# led_driver_v2.net
KiCad netlist of a schematic drawn in EAGLE
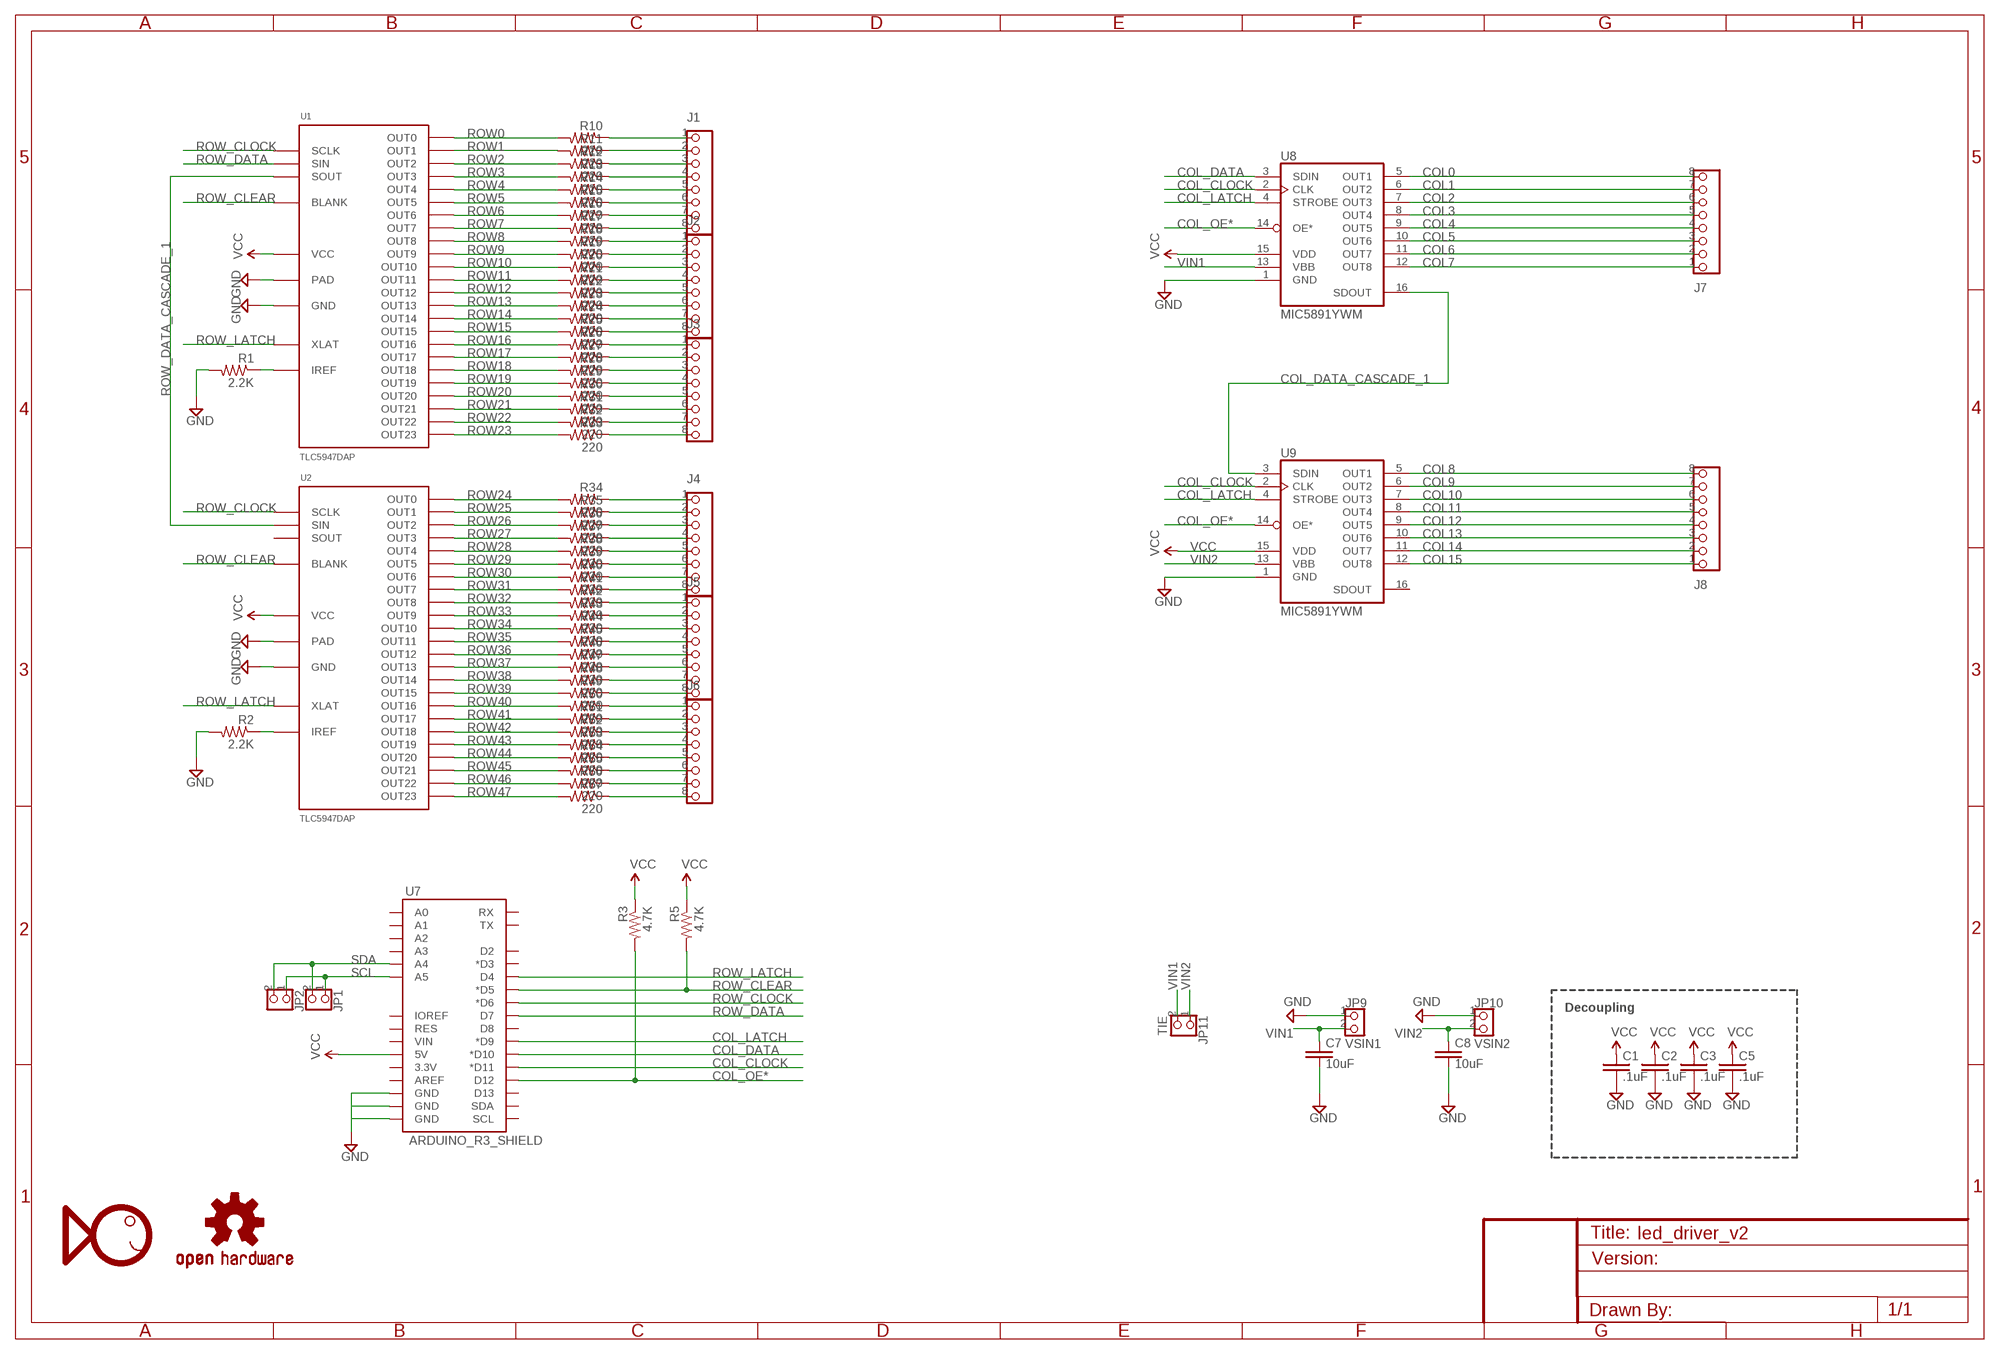
[diagram p0: schematic, sheet 1]

(export (version "E")
  (design (tool "Eeschema 10.0.6"))
  (components
    (comp (ref "C1")
      (value ".1uF")
      (footprint "eagle-import:C0603")
      (libsource (lib "eagle-import") (part "CAPACITORC0603"))
    )
    (comp (ref "C2")
      (value ".1uF")
      (footprint "eagle-import:C0603")
      (libsource (lib "eagle-import") (part "CAPACITORC0603"))
    )
    (comp (ref "C3")
      (value ".1uF")
      (footprint "eagle-import:C0603")
      (libsource (lib "eagle-import") (part "CAPACITORC0603"))
    )
    (comp (ref "C5")
      (value ".1uF")
      (footprint "eagle-import:C0603")
      (libsource (lib "eagle-import") (part "CAPACITORC0603"))
    )
    (comp (ref "C7")
      (value "10uF")
      (footprint "eagle-import:C0603")
      (libsource (lib "eagle-import") (part "CAPACITORC0603"))
    )
    (comp (ref "C8")
      (value "10uF")
      (footprint "eagle-import:C0603")
      (libsource (lib "eagle-import") (part "CAPACITORC0603"))
    )
    (comp (ref "FHI_LOGO")
      (value "FHI_LOGO")
      (footprint "eagle-import:FHI_LOGO")
      (libsource (lib "eagle-import") (part "FHI_LOGO"))
    )
    (comp (ref "J1")
      (value "PINHD-1X8")
      (footprint "eagle-import:1X08")
      (libsource (lib "eagle-import") (part "PINHD-1X8"))
    )
    (comp (ref "J2")
      (value "PINHD-1X8")
      (footprint "eagle-import:1X08")
      (libsource (lib "eagle-import") (part "PINHD-1X8"))
    )
    (comp (ref "J3")
      (value "PINHD-1X8")
      (footprint "eagle-import:1X08")
      (libsource (lib "eagle-import") (part "PINHD-1X8"))
    )
    (comp (ref "J4")
      (value "PINHD-1X8")
      (footprint "eagle-import:1X08")
      (libsource (lib "eagle-import") (part "PINHD-1X8"))
    )
    (comp (ref "J5")
      (value "PINHD-1X8")
      (footprint "eagle-import:1X08")
      (libsource (lib "eagle-import") (part "PINHD-1X8"))
    )
    (comp (ref "J6")
      (value "PINHD-1X8")
      (footprint "eagle-import:1X08")
      (libsource (lib "eagle-import") (part "PINHD-1X8"))
    )
    (comp (ref "J7")
      (value "PINHD-1X8")
      (footprint "eagle-import:1X08")
      (libsource (lib "eagle-import") (part "PINHD-1X8"))
    )
    (comp (ref "J8")
      (value "PINHD-1X8")
      (footprint "eagle-import:1X08")
      (libsource (lib "eagle-import") (part "PINHD-1X8"))
    )
    (comp (ref "JP1")
      (value "PINHD-1X2")
      (footprint "eagle-import:1X02")
      (libsource (lib "eagle-import") (part "PINHD-1X2"))
    )
    (comp (ref "JP2")
      (value "PINHD-1X2")
      (footprint "eagle-import:1X02")
      (libsource (lib "eagle-import") (part "PINHD-1X2"))
    )
    (comp (ref "JP9")
      (value "VSIN1")
      (footprint "eagle-import:1X02")
      (libsource (lib "eagle-import") (part "PINHD-1X2"))
    )
    (comp (ref "JP10")
      (value "VSIN2")
      (footprint "eagle-import:1X02")
      (libsource (lib "eagle-import") (part "PINHD-1X2"))
    )
    (comp (ref "JP11")
      (value "TIE")
      (footprint "eagle-import:1X02")
      (libsource (lib "eagle-import") (part "PINHD-1X2"))
    )
    (comp (ref "OHW_LOGO")
      (value "OSHW-LOGOS")
      (footprint "eagle-import:OSHW-LOGO-S")
      (libsource (lib "eagle-import") (part "OSHW-LOGOS"))
    )
    (comp (ref "R1")
      (value "2.2K")
      (footprint "eagle-import:0603-RES")
      (libsource (lib "eagle-import") (part "RESISTOR_SMD0603-RES"))
    )
    (comp (ref "R2")
      (value "2.2K")
      (footprint "eagle-import:0603-RES")
      (libsource (lib "eagle-import") (part "RESISTOR_SMD0603-RES"))
    )
    (comp (ref "R3")
      (value "4.7K")
      (footprint "eagle-import:0603-RES")
      (libsource (lib "eagle-import") (part "RESISTOR_SMD0603-RES"))
    )
    (comp (ref "R5")
      (value "4.7K")
      (footprint "eagle-import:0603-RES")
      (libsource (lib "eagle-import") (part "RESISTOR_SMD0603-RES"))
    )
    (comp (ref "R10")
      (value "220")
      (footprint "eagle-import:0603-RES")
      (libsource (lib "eagle-import") (part "RESISTOR_SMD0603-RES"))
    )
    (comp (ref "R11")
      (value "220")
      (footprint "eagle-import:0603-RES")
      (libsource (lib "eagle-import") (part "RESISTOR_SMD0603-RES"))
    )
    (comp (ref "R12")
      (value "220")
      (footprint "eagle-import:0603-RES")
      (libsource (lib "eagle-import") (part "RESISTOR_SMD0603-RES"))
    )
    (comp (ref "R13")
      (value "220")
      (footprint "eagle-import:0603-RES")
      (libsource (lib "eagle-import") (part "RESISTOR_SMD0603-RES"))
    )
    (comp (ref "R14")
      (value "220")
      (footprint "eagle-import:0603-RES")
      (libsource (lib "eagle-import") (part "RESISTOR_SMD0603-RES"))
    )
    (comp (ref "R15")
      (value "220")
      (footprint "eagle-import:0603-RES")
      (libsource (lib "eagle-import") (part "RESISTOR_SMD0603-RES"))
    )
    (comp (ref "R16")
      (value "220")
      (footprint "eagle-import:0603-RES")
      (libsource (lib "eagle-import") (part "RESISTOR_SMD0603-RES"))
    )
    (comp (ref "R17")
      (value "220")
      (footprint "eagle-import:0603-RES")
      (libsource (lib "eagle-import") (part "RESISTOR_SMD0603-RES"))
    )
    (comp (ref "R18")
      (value "220")
      (footprint "eagle-import:0603-RES")
      (libsource (lib "eagle-import") (part "RESISTOR_SMD0603-RES"))
    )
    (comp (ref "R19")
      (value "220")
      (footprint "eagle-import:0603-RES")
      (libsource (lib "eagle-import") (part "RESISTOR_SMD0603-RES"))
    )
    (comp (ref "R20")
      (value "220")
      (footprint "eagle-import:0603-RES")
      (libsource (lib "eagle-import") (part "RESISTOR_SMD0603-RES"))
    )
    (comp (ref "R21")
      (value "220")
      (footprint "eagle-import:0603-RES")
      (libsource (lib "eagle-import") (part "RESISTOR_SMD0603-RES"))
    )
    (comp (ref "R22")
      (value "220")
      (footprint "eagle-import:0603-RES")
      (libsource (lib "eagle-import") (part "RESISTOR_SMD0603-RES"))
    )
    (comp (ref "R23")
      (value "220")
      (footprint "eagle-import:0603-RES")
      (libsource (lib "eagle-import") (part "RESISTOR_SMD0603-RES"))
    )
    (comp (ref "R24")
      (value "220")
      (footprint "eagle-import:0603-RES")
      (libsource (lib "eagle-import") (part "RESISTOR_SMD0603-RES"))
    )
    (comp (ref "R25")
      (value "220")
      (footprint "eagle-import:0603-RES")
      (libsource (lib "eagle-import") (part "RESISTOR_SMD0603-RES"))
    )
    (comp (ref "R26")
      (value "220")
      (footprint "eagle-import:0603-RES")
      (libsource (lib "eagle-import") (part "RESISTOR_SMD0603-RES"))
    )
    (comp (ref "R27")
      (value "220")
      (footprint "eagle-import:0603-RES")
      (libsource (lib "eagle-import") (part "RESISTOR_SMD0603-RES"))
    )
    (comp (ref "R28")
      (value "220")
      (footprint "eagle-import:0603-RES")
      (libsource (lib "eagle-import") (part "RESISTOR_SMD0603-RES"))
    )
    (comp (ref "R29")
      (value "220")
      (footprint "eagle-import:0603-RES")
      (libsource (lib "eagle-import") (part "RESISTOR_SMD0603-RES"))
    )
    (comp (ref "R30")
      (value "220")
      (footprint "eagle-import:0603-RES")
      (libsource (lib "eagle-import") (part "RESISTOR_SMD0603-RES"))
    )
    (comp (ref "R31")
      (value "220")
      (footprint "eagle-import:0603-RES")
      (libsource (lib "eagle-import") (part "RESISTOR_SMD0603-RES"))
    )
    (comp (ref "R32")
      (value "220")
      (footprint "eagle-import:0603-RES")
      (libsource (lib "eagle-import") (part "RESISTOR_SMD0603-RES"))
    )
    (comp (ref "R33")
      (value "220")
      (footprint "eagle-import:0603-RES")
      (libsource (lib "eagle-import") (part "RESISTOR_SMD0603-RES"))
    )
    (comp (ref "R34")
      (value "220")
      (footprint "eagle-import:0603-RES")
      (libsource (lib "eagle-import") (part "RESISTOR_SMD0603-RES"))
    )
    (comp (ref "R35")
      (value "220")
      (footprint "eagle-import:0603-RES")
      (libsource (lib "eagle-import") (part "RESISTOR_SMD0603-RES"))
    )
    (comp (ref "R36")
      (value "220")
      (footprint "eagle-import:0603-RES")
      (libsource (lib "eagle-import") (part "RESISTOR_SMD0603-RES"))
    )
    (comp (ref "R37")
      (value "220")
      (footprint "eagle-import:0603-RES")
      (libsource (lib "eagle-import") (part "RESISTOR_SMD0603-RES"))
    )
    (comp (ref "R38")
      (value "220")
      (footprint "eagle-import:0603-RES")
      (libsource (lib "eagle-import") (part "RESISTOR_SMD0603-RES"))
    )
    (comp (ref "R39")
      (value "220")
      (footprint "eagle-import:0603-RES")
      (libsource (lib "eagle-import") (part "RESISTOR_SMD0603-RES"))
    )
    (comp (ref "R40")
      (value "220")
      (footprint "eagle-import:0603-RES")
      (libsource (lib "eagle-import") (part "RESISTOR_SMD0603-RES"))
    )
    (comp (ref "R41")
      (value "220")
      (footprint "eagle-import:0603-RES")
      (libsource (lib "eagle-import") (part "RESISTOR_SMD0603-RES"))
    )
    (comp (ref "R42")
      (value "220")
      (footprint "eagle-import:0603-RES")
      (libsource (lib "eagle-import") (part "RESISTOR_SMD0603-RES"))
    )
    (comp (ref "R43")
      (value "220")
      (footprint "eagle-import:0603-RES")
      (libsource (lib "eagle-import") (part "RESISTOR_SMD0603-RES"))
    )
    (comp (ref "R44")
      (value "220")
      (footprint "eagle-import:0603-RES")
      (libsource (lib "eagle-import") (part "RESISTOR_SMD0603-RES"))
    )
    (comp (ref "R45")
      (value "220")
      (footprint "eagle-import:0603-RES")
      (libsource (lib "eagle-import") (part "RESISTOR_SMD0603-RES"))
    )
    (comp (ref "R46")
      (value "220")
      (footprint "eagle-import:0603-RES")
      (libsource (lib "eagle-import") (part "RESISTOR_SMD0603-RES"))
    )
    (comp (ref "R47")
      (value "220")
      (footprint "eagle-import:0603-RES")
      (libsource (lib "eagle-import") (part "RESISTOR_SMD0603-RES"))
    )
    (comp (ref "R48")
      (value "220")
      (footprint "eagle-import:0603-RES")
      (libsource (lib "eagle-import") (part "RESISTOR_SMD0603-RES"))
    )
    (comp (ref "R49")
      (value "220")
      (footprint "eagle-import:0603-RES")
      (libsource (lib "eagle-import") (part "RESISTOR_SMD0603-RES"))
    )
    (comp (ref "R50")
      (value "220")
      (footprint "eagle-import:0603-RES")
      (libsource (lib "eagle-import") (part "RESISTOR_SMD0603-RES"))
    )
    (comp (ref "R51")
      (value "220")
      (footprint "eagle-import:0603-RES")
      (libsource (lib "eagle-import") (part "RESISTOR_SMD0603-RES"))
    )
    (comp (ref "R52")
      (value "220")
      (footprint "eagle-import:0603-RES")
      (libsource (lib "eagle-import") (part "RESISTOR_SMD0603-RES"))
    )
    (comp (ref "R53")
      (value "220")
      (footprint "eagle-import:0603-RES")
      (libsource (lib "eagle-import") (part "RESISTOR_SMD0603-RES"))
    )
    (comp (ref "R54")
      (value "220")
      (footprint "eagle-import:0603-RES")
      (libsource (lib "eagle-import") (part "RESISTOR_SMD0603-RES"))
    )
    (comp (ref "R55")
      (value "220")
      (footprint "eagle-import:0603-RES")
      (libsource (lib "eagle-import") (part "RESISTOR_SMD0603-RES"))
    )
    (comp (ref "R56")
      (value "220")
      (footprint "eagle-import:0603-RES")
      (libsource (lib "eagle-import") (part "RESISTOR_SMD0603-RES"))
    )
    (comp (ref "R57")
      (value "220")
      (footprint "eagle-import:0603-RES")
      (libsource (lib "eagle-import") (part "RESISTOR_SMD0603-RES"))
    )
    (comp (ref "U1")
      (value "TLC5947DAP")
      (footprint "eagle-import:HTSSOP32DAP")
      (libsource (lib "eagle-import") (part "TLC5947DAP"))
    )
    (comp (ref "U2")
      (value "TLC5947DAP")
      (footprint "eagle-import:HTSSOP32DAP")
      (libsource (lib "eagle-import") (part "TLC5947DAP"))
    )
    (comp (ref "U7")
      (value "ARDUINO_R3_SHIELD")
      (footprint "eagle-import:UNO_R3_SHIELD")
      (libsource (lib "eagle-import") (part "ARDUINO_R3_SHIELD"))
    )
    (comp (ref "U8")
      (value "MIC5891YWM")
      (footprint "eagle-import:SO16")
      (libsource (lib "eagle-import") (part "MIC5891YWM"))
    )
    (comp (ref "U9")
      (value "MIC5891YWM")
      (footprint "eagle-import:SO16")
      (libsource (lib "eagle-import") (part "MIC5891YWM"))
    )
  )
  (nets
    (net (code "1") (name "/COL0") (class "Default")
      (node (ref "J7") (pin "8") (pinfunction "8_8") (pintype "passive"))
      (node (ref "U8") (pin "5") (pinfunction "OUT1_5") (pintype "tri_state"))
    )
    (net (code "2") (name "/COL1") (class "Default")
      (node (ref "J7") (pin "7") (pinfunction "7_7") (pintype "passive"))
      (node (ref "U8") (pin "6") (pinfunction "OUT2_6") (pintype "tri_state"))
    )
    (net (code "3") (name "/COL2") (class "Default")
      (node (ref "J7") (pin "6") (pinfunction "6_6") (pintype "passive"))
      (node (ref "U8") (pin "7") (pinfunction "OUT3_7") (pintype "tri_state"))
    )
    (net (code "4") (name "/COL3") (class "Default")
      (node (ref "J7") (pin "5") (pinfunction "5_5") (pintype "passive"))
      (node (ref "U8") (pin "8") (pinfunction "OUT4_8") (pintype "tri_state"))
    )
    (net (code "5") (name "/COL4") (class "Default")
      (node (ref "J7") (pin "4") (pinfunction "4_4") (pintype "passive"))
      (node (ref "U8") (pin "9") (pinfunction "OUT5_9") (pintype "tri_state"))
    )
    (net (code "6") (name "/COL5") (class "Default")
      (node (ref "J7") (pin "3") (pinfunction "3_3") (pintype "passive"))
      (node (ref "U8") (pin "10") (pinfunction "OUT6_10") (pintype "tri_state"))
    )
    (net (code "7") (name "/COL6") (class "Default")
      (node (ref "J7") (pin "2") (pinfunction "2_2") (pintype "passive"))
      (node (ref "U8") (pin "11") (pinfunction "OUT7_11") (pintype "tri_state"))
    )
    (net (code "8") (name "/COL7") (class "Default")
      (node (ref "J7") (pin "1") (pinfunction "1_1") (pintype "passive"))
      (node (ref "U8") (pin "12") (pinfunction "OUT8_12") (pintype "tri_state"))
    )
    (net (code "9") (name "/COL8") (class "Default")
      (node (ref "J8") (pin "8") (pinfunction "8_8") (pintype "passive"))
      (node (ref "U9") (pin "5") (pinfunction "OUT1_5") (pintype "tri_state"))
    )
    (net (code "10") (name "/COL9") (class "Default")
      (node (ref "J8") (pin "7") (pinfunction "7_7") (pintype "passive"))
      (node (ref "U9") (pin "6") (pinfunction "OUT2_6") (pintype "tri_state"))
    )
    (net (code "11") (name "/COL10") (class "Default")
      (node (ref "J8") (pin "6") (pinfunction "6_6") (pintype "passive"))
      (node (ref "U9") (pin "7") (pinfunction "OUT3_7") (pintype "tri_state"))
    )
    (net (code "12") (name "/COL11") (class "Default")
      (node (ref "J8") (pin "5") (pinfunction "5_5") (pintype "passive"))
      (node (ref "U9") (pin "8") (pinfunction "OUT4_8") (pintype "tri_state"))
    )
    (net (code "13") (name "/COL12") (class "Default")
      (node (ref "J8") (pin "4") (pinfunction "4_4") (pintype "passive"))
      (node (ref "U9") (pin "9") (pinfunction "OUT5_9") (pintype "tri_state"))
    )
    (net (code "14") (name "/COL13") (class "Default")
      (node (ref "J8") (pin "3") (pinfunction "3_3") (pintype "passive"))
      (node (ref "U9") (pin "10") (pinfunction "OUT6_10") (pintype "tri_state"))
    )
    (net (code "15") (name "/COL14") (class "Default")
      (node (ref "J8") (pin "2") (pinfunction "2_2") (pintype "passive"))
      (node (ref "U9") (pin "11") (pinfunction "OUT7_11") (pintype "tri_state"))
    )
    (net (code "16") (name "/COL15") (class "Default")
      (node (ref "J8") (pin "1") (pinfunction "1_1") (pintype "passive"))
      (node (ref "U9") (pin "12") (pinfunction "OUT8_12") (pintype "tri_state"))
    )
    (net (code "17") (name "/COL_CLOCK") (class "Default")
      (node (ref "U7") (pin "D11") (pinfunction "*D11_D11") (pintype "bidirectional"))
      (node (ref "U8") (pin "2") (pinfunction "CLK_2") (pintype "input"))
      (node (ref "U9") (pin "2") (pinfunction "CLK_2") (pintype "input"))
    )
    (net (code "18") (name "/COL_DATA") (class "Default")
      (node (ref "U7") (pin "D10") (pinfunction "*D10_D10") (pintype "bidirectional"))
      (node (ref "U8") (pin "3") (pinfunction "SDIN_3") (pintype "input"))
    )
    (net (code "19") (name "/COL_DATA_CASCADE_1") (class "Default")
      (node (ref "U8") (pin "16") (pinfunction "SDOUT_16") (pintype "output"))
      (node (ref "U9") (pin "3") (pinfunction "SDIN_3") (pintype "input"))
    )
    (net (code "20") (name "/COL_LATCH") (class "Default")
      (node (ref "U7") (pin "D9") (pinfunction "*D9_D9") (pintype "bidirectional"))
      (node (ref "U8") (pin "4") (pinfunction "STROBE_4") (pintype "input"))
      (node (ref "U9") (pin "4") (pinfunction "STROBE_4") (pintype "input"))
    )
    (net (code "21") (name "/COL_OE*") (class "Default")
      (node (ref "R3") (pin "2") (pinfunction "2_2") (pintype "passive"))
      (node (ref "U7") (pin "D12") (pinfunction "D12_D12") (pintype "bidirectional"))
      (node (ref "U8") (pin "14") (pinfunction "OE*_14") (pintype "input"))
      (node (ref "U9") (pin "14") (pinfunction "OE*_14") (pintype "input"))
    )
    (net (code "22") (name "/ROW0") (class "Default")
      (node (ref "R10") (pin "2") (pinfunction "2_2") (pintype "passive"))
      (node (ref "U1") (pin "5") (pinfunction "OUT0_5") (pintype "bidirectional"))
    )
    (net (code "23") (name "/ROW1") (class "Default")
      (node (ref "R11") (pin "2") (pinfunction "2_2") (pintype "passive"))
      (node (ref "U1") (pin "6") (pinfunction "OUT1_6") (pintype "bidirectional"))
    )
    (net (code "24") (name "/ROW2") (class "Default")
      (node (ref "R12") (pin "2") (pinfunction "2_2") (pintype "passive"))
      (node (ref "U1") (pin "7") (pinfunction "OUT2_7") (pintype "bidirectional"))
    )
    (net (code "25") (name "/ROW3") (class "Default")
      (node (ref "R13") (pin "2") (pinfunction "2_2") (pintype "passive"))
      (node (ref "U1") (pin "8") (pinfunction "OUT3_8") (pintype "bidirectional"))
    )
    (net (code "26") (name "/ROW4") (class "Default")
      (node (ref "R14") (pin "2") (pinfunction "2_2") (pintype "passive"))
      (node (ref "U1") (pin "9") (pinfunction "OUT4_9") (pintype "bidirectional"))
    )
    (net (code "27") (name "/ROW5") (class "Default")
      (node (ref "R15") (pin "2") (pinfunction "2_2") (pintype "passive"))
      (node (ref "U1") (pin "10") (pinfunction "OUT5_10") (pintype "bidirectional"))
    )
    (net (code "28") (name "/ROW6") (class "Default")
      (node (ref "R16") (pin "2") (pinfunction "2_2") (pintype "passive"))
      (node (ref "U1") (pin "11") (pinfunction "OUT6_11") (pintype "bidirectional"))
    )
    (net (code "29") (name "/ROW7") (class "Default")
      (node (ref "R17") (pin "2") (pinfunction "2_2") (pintype "passive"))
      (node (ref "U1") (pin "12") (pinfunction "OUT7_12") (pintype "bidirectional"))
    )
    (net (code "30") (name "/ROW8") (class "Default")
      (node (ref "R18") (pin "2") (pinfunction "2_2") (pintype "passive"))
      (node (ref "U1") (pin "13") (pinfunction "OUT8_13") (pintype "bidirectional"))
    )
    (net (code "31") (name "/ROW9") (class "Default")
      (node (ref "R19") (pin "2") (pinfunction "2_2") (pintype "passive"))
      (node (ref "U1") (pin "14") (pinfunction "OUT9_14") (pintype "bidirectional"))
    )
    (net (code "32") (name "/ROW10") (class "Default")
      (node (ref "R20") (pin "2") (pinfunction "2_2") (pintype "passive"))
      (node (ref "U1") (pin "15") (pinfunction "OUT10_15") (pintype "bidirectional"))
    )
    (net (code "33") (name "/ROW11") (class "Default")
      (node (ref "R21") (pin "2") (pinfunction "2_2") (pintype "passive"))
      (node (ref "U1") (pin "16") (pinfunction "OUT11_16") (pintype "bidirectional"))
    )
    (net (code "34") (name "/ROW12") (class "Default")
      (node (ref "R22") (pin "2") (pinfunction "2_2") (pintype "passive"))
      (node (ref "U1") (pin "17") (pinfunction "OUT12_17") (pintype "bidirectional"))
    )
    (net (code "35") (name "/ROW13") (class "Default")
      (node (ref "R23") (pin "2") (pinfunction "2_2") (pintype "passive"))
      (node (ref "U1") (pin "18") (pinfunction "OUT13_18") (pintype "bidirectional"))
    )
    (net (code "36") (name "/ROW14") (class "Default")
      (node (ref "R24") (pin "2") (pinfunction "2_2") (pintype "passive"))
      (node (ref "U1") (pin "19") (pinfunction "OUT14_19") (pintype "bidirectional"))
    )
    (net (code "37") (name "/ROW15") (class "Default")
      (node (ref "R25") (pin "2") (pinfunction "2_2") (pintype "passive"))
      (node (ref "U1") (pin "20") (pinfunction "OUT15_20") (pintype "bidirectional"))
    )
    (net (code "38") (name "/ROW16") (class "Default")
      (node (ref "R26") (pin "2") (pinfunction "2_2") (pintype "passive"))
      (node (ref "U1") (pin "21") (pinfunction "OUT16_21") (pintype "bidirectional"))
    )
    (net (code "39") (name "/ROW17") (class "Default")
      (node (ref "R27") (pin "2") (pinfunction "2_2") (pintype "passive"))
      (node (ref "U1") (pin "22") (pinfunction "OUT17_22") (pintype "bidirectional"))
    )
    (net (code "40") (name "/ROW18") (class "Default")
      (node (ref "R28") (pin "2") (pinfunction "2_2") (pintype "passive"))
      (node (ref "U1") (pin "23") (pinfunction "OUT18_23") (pintype "bidirectional"))
    )
    (net (code "41") (name "/ROW19") (class "Default")
      (node (ref "R29") (pin "2") (pinfunction "2_2") (pintype "passive"))
      (node (ref "U1") (pin "24") (pinfunction "OUT19_24") (pintype "bidirectional"))
    )
    (net (code "42") (name "/ROW20") (class "Default")
      (node (ref "R30") (pin "2") (pinfunction "2_2") (pintype "passive"))
      (node (ref "U1") (pin "25") (pinfunction "OUT20_25") (pintype "bidirectional"))
    )
    (net (code "43") (name "/ROW21") (class "Default")
      (node (ref "R31") (pin "2") (pinfunction "2_2") (pintype "passive"))
      (node (ref "U1") (pin "26") (pinfunction "OUT21_26") (pintype "bidirectional"))
    )
    (net (code "44") (name "/ROW22") (class "Default")
      (node (ref "R32") (pin "2") (pinfunction "2_2") (pintype "passive"))
      (node (ref "U1") (pin "27") (pinfunction "OUT22_27") (pintype "bidirectional"))
    )
    (net (code "45") (name "/ROW23") (class "Default")
      (node (ref "R33") (pin "2") (pinfunction "2_2") (pintype "passive"))
      (node (ref "U1") (pin "28") (pinfunction "OUT23_28") (pintype "bidirectional"))
    )
    (net (code "46") (name "/ROW24") (class "Default")
      (node (ref "R34") (pin "2") (pinfunction "2_2") (pintype "passive"))
      (node (ref "U2") (pin "5") (pinfunction "OUT0_5") (pintype "bidirectional"))
    )
    (net (code "47") (name "/ROW25") (class "Default")
      (node (ref "R35") (pin "2") (pinfunction "2_2") (pintype "passive"))
      (node (ref "U2") (pin "6") (pinfunction "OUT1_6") (pintype "bidirectional"))
    )
    (net (code "48") (name "/ROW26") (class "Default")
      (node (ref "R36") (pin "2") (pinfunction "2_2") (pintype "passive"))
      (node (ref "U2") (pin "7") (pinfunction "OUT2_7") (pintype "bidirectional"))
    )
    (net (code "49") (name "/ROW27") (class "Default")
      (node (ref "R37") (pin "2") (pinfunction "2_2") (pintype "passive"))
      (node (ref "U2") (pin "8") (pinfunction "OUT3_8") (pintype "bidirectional"))
    )
    (net (code "50") (name "/ROW28") (class "Default")
      (node (ref "R38") (pin "2") (pinfunction "2_2") (pintype "passive"))
      (node (ref "U2") (pin "9") (pinfunction "OUT4_9") (pintype "bidirectional"))
    )
    (net (code "51") (name "/ROW29") (class "Default")
      (node (ref "R39") (pin "2") (pinfunction "2_2") (pintype "passive"))
      (node (ref "U2") (pin "10") (pinfunction "OUT5_10") (pintype "bidirectional"))
    )
    (net (code "52") (name "/ROW30") (class "Default")
      (node (ref "R40") (pin "2") (pinfunction "2_2") (pintype "passive"))
      (node (ref "U2") (pin "11") (pinfunction "OUT6_11") (pintype "bidirectional"))
    )
    (net (code "53") (name "/ROW31") (class "Default")
      (node (ref "R41") (pin "2") (pinfunction "2_2") (pintype "passive"))
      (node (ref "U2") (pin "12") (pinfunction "OUT7_12") (pintype "bidirectional"))
    )
    (net (code "54") (name "/ROW32") (class "Default")
      (node (ref "R42") (pin "2") (pinfunction "2_2") (pintype "passive"))
      (node (ref "U2") (pin "13") (pinfunction "OUT8_13") (pintype "bidirectional"))
    )
    (net (code "55") (name "/ROW33") (class "Default")
      (node (ref "R43") (pin "2") (pinfunction "2_2") (pintype "passive"))
      (node (ref "U2") (pin "14") (pinfunction "OUT9_14") (pintype "bidirectional"))
    )
    (net (code "56") (name "/ROW34") (class "Default")
      (node (ref "R44") (pin "2") (pinfunction "2_2") (pintype "passive"))
      (node (ref "U2") (pin "15") (pinfunction "OUT10_15") (pintype "bidirectional"))
    )
    (net (code "57") (name "/ROW35") (class "Default")
      (node (ref "R45") (pin "2") (pinfunction "2_2") (pintype "passive"))
      (node (ref "U2") (pin "16") (pinfunction "OUT11_16") (pintype "bidirectional"))
    )
    (net (code "58") (name "/ROW36") (class "Default")
      (node (ref "R46") (pin "2") (pinfunction "2_2") (pintype "passive"))
      (node (ref "U2") (pin "17") (pinfunction "OUT12_17") (pintype "bidirectional"))
    )
    (net (code "59") (name "/ROW37") (class "Default")
      (node (ref "R47") (pin "2") (pinfunction "2_2") (pintype "passive"))
      (node (ref "U2") (pin "18") (pinfunction "OUT13_18") (pintype "bidirectional"))
    )
    (net (code "60") (name "/ROW38") (class "Default")
      (node (ref "R48") (pin "2") (pinfunction "2_2") (pintype "passive"))
      (node (ref "U2") (pin "19") (pinfunction "OUT14_19") (pintype "bidirectional"))
    )
    (net (code "61") (name "/ROW39") (class "Default")
      (node (ref "R49") (pin "2") (pinfunction "2_2") (pintype "passive"))
      (node (ref "U2") (pin "20") (pinfunction "OUT15_20") (pintype "bidirectional"))
    )
    (net (code "62") (name "/ROW40") (class "Default")
      (node (ref "R50") (pin "2") (pinfunction "2_2") (pintype "passive"))
      (node (ref "U2") (pin "21") (pinfunction "OUT16_21") (pintype "bidirectional"))
    )
    (net (code "63") (name "/ROW41") (class "Default")
      (node (ref "R51") (pin "2") (pinfunction "2_2") (pintype "passive"))
      (node (ref "U2") (pin "22") (pinfunction "OUT17_22") (pintype "bidirectional"))
    )
    (net (code "64") (name "/ROW42") (class "Default")
      (node (ref "R52") (pin "2") (pinfunction "2_2") (pintype "passive"))
      (node (ref "U2") (pin "23") (pinfunction "OUT18_23") (pintype "bidirectional"))
    )
    (net (code "65") (name "/ROW43") (class "Default")
      (node (ref "R53") (pin "2") (pinfunction "2_2") (pintype "passive"))
      (node (ref "U2") (pin "24") (pinfunction "OUT19_24") (pintype "bidirectional"))
    )
    (net (code "66") (name "/ROW44") (class "Default")
      (node (ref "R54") (pin "2") (pinfunction "2_2") (pintype "passive"))
      (node (ref "U2") (pin "25") (pinfunction "OUT20_25") (pintype "bidirectional"))
    )
    (net (code "67") (name "/ROW45") (class "Default")
      (node (ref "R55") (pin "2") (pinfunction "2_2") (pintype "passive"))
      (node (ref "U2") (pin "26") (pinfunction "OUT21_26") (pintype "bidirectional"))
    )
    (net (code "68") (name "/ROW46") (class "Default")
      (node (ref "R56") (pin "2") (pinfunction "2_2") (pintype "passive"))
      (node (ref "U2") (pin "27") (pinfunction "OUT22_27") (pintype "bidirectional"))
    )
    (net (code "69") (name "/ROW47") (class "Default")
      (node (ref "R57") (pin "2") (pinfunction "2_2") (pintype "passive"))
      (node (ref "U2") (pin "28") (pinfunction "OUT23_28") (pintype "bidirectional"))
    )
    (net (code "70") (name "/ROW_CLEAR") (class "Default")
      (node (ref "R5") (pin "2") (pinfunction "2_2") (pintype "passive"))
      (node (ref "U1") (pin "2") (pinfunction "BLANK_2") (pintype "bidirectional"))
      (node (ref "U2") (pin "2") (pinfunction "BLANK_2") (pintype "bidirectional"))
      (node (ref "U7") (pin "D5") (pinfunction "*D5_D5") (pintype "bidirectional"))
    )
    (net (code "71") (name "/ROW_CLOCK") (class "Default")
      (node (ref "U1") (pin "3") (pinfunction "SCLK_3") (pintype "bidirectional"))
      (node (ref "U2") (pin "3") (pinfunction "SCLK_3") (pintype "bidirectional"))
      (node (ref "U7") (pin "D6") (pinfunction "*D6_D6") (pintype "bidirectional"))
    )
    (net (code "72") (name "/ROW_DATA") (class "Default")
      (node (ref "U1") (pin "4") (pinfunction "SIN_4") (pintype "bidirectional"))
      (node (ref "U7") (pin "D7") (pinfunction "D7_D7") (pintype "bidirectional"))
    )
    (net (code "73") (name "/ROW_DATA_CASCADE_1") (class "Default")
      (node (ref "U1") (pin "29") (pinfunction "SOUT_29") (pintype "bidirectional"))
      (node (ref "U2") (pin "4") (pinfunction "SIN_4") (pintype "bidirectional"))
    )
    (net (code "74") (name "/ROW_LATCH") (class "Default")
      (node (ref "U1") (pin "30") (pinfunction "XLAT_30") (pintype "bidirectional"))
      (node (ref "U2") (pin "30") (pinfunction "XLAT_30") (pintype "bidirectional"))
      (node (ref "U7") (pin "D4") (pinfunction "D4_D4") (pintype "bidirectional"))
    )
    (net (code "75") (name "/SCL") (class "Default")
      (node (ref "JP1") (pin "1") (pinfunction "1_1") (pintype "passive"))
      (node (ref "JP2") (pin "1") (pinfunction "1_1") (pintype "passive"))
      (node (ref "U7") (pin "A5") (pinfunction "A5_A5") (pintype "bidirectional"))
    )
    (net (code "76") (name "/SDA") (class "Default")
      (node (ref "JP1") (pin "2") (pinfunction "2_2") (pintype "passive"))
      (node (ref "JP2") (pin "2") (pinfunction "2_2") (pintype "passive"))
      (node (ref "U7") (pin "A4") (pinfunction "A4_A4") (pintype "bidirectional"))
    )
    (net (code "77") (name "/VIN1") (class "Default")
      (node (ref "C7") (pin "1") (pinfunction "1_1") (pintype "passive"))
      (node (ref "JP11") (pin "2") (pinfunction "2_2") (pintype "passive"))
      (node (ref "JP9") (pin "2") (pinfunction "2_2") (pintype "passive"))
      (node (ref "U8") (pin "13") (pinfunction "VBB_13") (pintype "power_in"))
    )
    (net (code "78") (name "/VIN2") (class "Default")
      (node (ref "C8") (pin "1") (pinfunction "1_1") (pintype "passive"))
      (node (ref "JP10") (pin "2") (pinfunction "2_2") (pintype "passive"))
      (node (ref "JP11") (pin "1") (pinfunction "1_1") (pintype "passive"))
      (node (ref "U9") (pin "13") (pinfunction "VBB_13") (pintype "power_in"))
    )
    (net (code "79") (name "GND") (class "Default")
      (node (ref "C1") (pin "2") (pinfunction "2_2") (pintype "passive"))
      (node (ref "C2") (pin "2") (pinfunction "2_2") (pintype "passive"))
      (node (ref "C3") (pin "2") (pinfunction "2_2") (pintype "passive"))
      (node (ref "C5") (pin "2") (pinfunction "2_2") (pintype "passive"))
      (node (ref "C7") (pin "2") (pinfunction "2_2") (pintype "passive"))
      (node (ref "C8") (pin "2") (pinfunction "2_2") (pintype "passive"))
      (node (ref "JP10") (pin "1") (pinfunction "1_1") (pintype "passive"))
      (node (ref "JP9") (pin "1") (pinfunction "1_1") (pintype "passive"))
      (node (ref "R1") (pin "2") (pinfunction "2_2") (pintype "passive"))
      (node (ref "R2") (pin "2") (pinfunction "2_2") (pintype "passive"))
      (node (ref "U1") (pin "1") (pinfunction "GND_1") (pintype "bidirectional"))
      (node (ref "U1") (pin "EXP") (pinfunction "PAD_EXP") (pintype "bidirectional"))
      (node (ref "U2") (pin "1") (pinfunction "GND_1") (pintype "bidirectional"))
      (node (ref "U2") (pin "EXP") (pinfunction "PAD_EXP") (pintype "bidirectional"))
      (node (ref "U7") (pin "GND@0") (pinfunction "GND_GND@0") (pintype "bidirectional"))
      (node (ref "U7") (pin "GND@1") (pinfunction "GND_GND@1") (pintype "bidirectional"))
      (node (ref "U7") (pin "GND@2") (pinfunction "GND_GND@2") (pintype "bidirectional"))
      (node (ref "U8") (pin "1") (pinfunction "GND_1") (pintype "power_in"))
      (node (ref "U9") (pin "1") (pinfunction "GND_1") (pintype "power_in"))
    )
    (net (code "80") (name "Net-(J1-Pad1)") (class "Default")
      (node (ref "J1") (pin "1") (pinfunction "1_1") (pintype "passive"))
      (node (ref "R10") (pin "1") (pinfunction "1_1") (pintype "passive"))
    )
    (net (code "81") (name "Net-(J1-Pad2)") (class "Default")
      (node (ref "J1") (pin "2") (pinfunction "2_2") (pintype "passive"))
      (node (ref "R11") (pin "1") (pinfunction "1_1") (pintype "passive"))
    )
    (net (code "82") (name "Net-(J1-Pad3)") (class "Default")
      (node (ref "J1") (pin "3") (pinfunction "3_3") (pintype "passive"))
      (node (ref "R12") (pin "1") (pinfunction "1_1") (pintype "passive"))
    )
    (net (code "83") (name "Net-(J1-Pad4)") (class "Default")
      (node (ref "J1") (pin "4") (pinfunction "4_4") (pintype "passive"))
      (node (ref "R13") (pin "1") (pinfunction "1_1") (pintype "passive"))
    )
    (net (code "84") (name "Net-(J1-Pad5)") (class "Default")
      (node (ref "J1") (pin "5") (pinfunction "5_5") (pintype "passive"))
      (node (ref "R14") (pin "1") (pinfunction "1_1") (pintype "passive"))
    )
    (net (code "85") (name "Net-(J1-Pad6)") (class "Default")
      (node (ref "J1") (pin "6") (pinfunction "6_6") (pintype "passive"))
      (node (ref "R15") (pin "1") (pinfunction "1_1") (pintype "passive"))
    )
    (net (code "86") (name "Net-(J1-Pad7)") (class "Default")
      (node (ref "J1") (pin "7") (pinfunction "7_7") (pintype "passive"))
      (node (ref "R16") (pin "1") (pinfunction "1_1") (pintype "passive"))
    )
    (net (code "87") (name "Net-(J1-Pad8)") (class "Default")
      (node (ref "J1") (pin "8") (pinfunction "8_8") (pintype "passive"))
      (node (ref "R17") (pin "1") (pinfunction "1_1") (pintype "passive"))
    )
    (net (code "88") (name "Net-(J2-Pad1)") (class "Default")
      (node (ref "J2") (pin "1") (pinfunction "1_1") (pintype "passive"))
      (node (ref "R18") (pin "1") (pinfunction "1_1") (pintype "passive"))
    )
    (net (code "89") (name "Net-(J2-Pad2)") (class "Default")
      (node (ref "J2") (pin "2") (pinfunction "2_2") (pintype "passive"))
      (node (ref "R19") (pin "1") (pinfunction "1_1") (pintype "passive"))
    )
    (net (code "90") (name "Net-(J2-Pad3)") (class "Default")
      (node (ref "J2") (pin "3") (pinfunction "3_3") (pintype "passive"))
      (node (ref "R20") (pin "1") (pinfunction "1_1") (pintype "passive"))
    )
    (net (code "91") (name "Net-(J2-Pad4)") (class "Default")
      (node (ref "J2") (pin "4") (pinfunction "4_4") (pintype "passive"))
      (node (ref "R21") (pin "1") (pinfunction "1_1") (pintype "passive"))
    )
    (net (code "92") (name "Net-(J2-Pad5)") (class "Default")
      (node (ref "J2") (pin "5") (pinfunction "5_5") (pintype "passive"))
      (node (ref "R22") (pin "1") (pinfunction "1_1") (pintype "passive"))
    )
    (net (code "93") (name "Net-(J2-Pad6)") (class "Default")
      (node (ref "J2") (pin "6") (pinfunction "6_6") (pintype "passive"))
      (node (ref "R23") (pin "1") (pinfunction "1_1") (pintype "passive"))
    )
    (net (code "94") (name "Net-(J2-Pad7)") (class "Default")
      (node (ref "J2") (pin "7") (pinfunction "7_7") (pintype "passive"))
      (node (ref "R24") (pin "1") (pinfunction "1_1") (pintype "passive"))
    )
    (net (code "95") (name "Net-(J2-Pad8)") (class "Default")
      (node (ref "J2") (pin "8") (pinfunction "8_8") (pintype "passive"))
      (node (ref "R25") (pin "1") (pinfunction "1_1") (pintype "passive"))
    )
    (net (code "96") (name "Net-(J3-Pad1)") (class "Default")
      (node (ref "J3") (pin "1") (pinfunction "1_1") (pintype "passive"))
      (node (ref "R26") (pin "1") (pinfunction "1_1") (pintype "passive"))
    )
    (net (code "97") (name "Net-(J3-Pad2)") (class "Default")
      (node (ref "J3") (pin "2") (pinfunction "2_2") (pintype "passive"))
      (node (ref "R27") (pin "1") (pinfunction "1_1") (pintype "passive"))
    )
    (net (code "98") (name "Net-(J3-Pad3)") (class "Default")
      (node (ref "J3") (pin "3") (pinfunction "3_3") (pintype "passive"))
      (node (ref "R28") (pin "1") (pinfunction "1_1") (pintype "passive"))
    )
    (net (code "99") (name "Net-(J3-Pad4)") (class "Default")
      (node (ref "J3") (pin "4") (pinfunction "4_4") (pintype "passive"))
      (node (ref "R29") (pin "1") (pinfunction "1_1") (pintype "passive"))
    )
    (net (code "100") (name "Net-(J3-Pad5)") (class "Default")
      (node (ref "J3") (pin "5") (pinfunction "5_5") (pintype "passive"))
      (node (ref "R30") (pin "1") (pinfunction "1_1") (pintype "passive"))
    )
    (net (code "101") (name "Net-(J3-Pad6)") (class "Default")
      (node (ref "J3") (pin "6") (pinfunction "6_6") (pintype "passive"))
      (node (ref "R31") (pin "1") (pinfunction "1_1") (pintype "passive"))
    )
    (net (code "102") (name "Net-(J3-Pad7)") (class "Default")
      (node (ref "J3") (pin "7") (pinfunction "7_7") (pintype "passive"))
      (node (ref "R32") (pin "1") (pinfunction "1_1") (pintype "passive"))
    )
    (net (code "103") (name "Net-(J3-Pad8)") (class "Default")
      (node (ref "J3") (pin "8") (pinfunction "8_8") (pintype "passive"))
      (node (ref "R33") (pin "1") (pinfunction "1_1") (pintype "passive"))
    )
    (net (code "104") (name "Net-(J4-Pad1)") (class "Default")
      (node (ref "J4") (pin "1") (pinfunction "1_1") (pintype "passive"))
      (node (ref "R34") (pin "1") (pinfunction "1_1") (pintype "passive"))
    )
    (net (code "105") (name "Net-(J4-Pad2)") (class "Default")
      (node (ref "J4") (pin "2") (pinfunction "2_2") (pintype "passive"))
      (node (ref "R35") (pin "1") (pinfunction "1_1") (pintype "passive"))
    )
    (net (code "106") (name "Net-(J4-Pad3)") (class "Default")
      (node (ref "J4") (pin "3") (pinfunction "3_3") (pintype "passive"))
      (node (ref "R36") (pin "1") (pinfunction "1_1") (pintype "passive"))
    )
    (net (code "107") (name "Net-(J4-Pad4)") (class "Default")
      (node (ref "J4") (pin "4") (pinfunction "4_4") (pintype "passive"))
      (node (ref "R37") (pin "1") (pinfunction "1_1") (pintype "passive"))
    )
    (net (code "108") (name "Net-(J4-Pad5)") (class "Default")
      (node (ref "J4") (pin "5") (pinfunction "5_5") (pintype "passive"))
      (node (ref "R38") (pin "1") (pinfunction "1_1") (pintype "passive"))
    )
    (net (code "109") (name "Net-(J4-Pad6)") (class "Default")
      (node (ref "J4") (pin "6") (pinfunction "6_6") (pintype "passive"))
      (node (ref "R39") (pin "1") (pinfunction "1_1") (pintype "passive"))
    )
    (net (code "110") (name "Net-(J4-Pad7)") (class "Default")
      (node (ref "J4") (pin "7") (pinfunction "7_7") (pintype "passive"))
      (node (ref "R40") (pin "1") (pinfunction "1_1") (pintype "passive"))
    )
    (net (code "111") (name "Net-(J4-Pad8)") (class "Default")
      (node (ref "J4") (pin "8") (pinfunction "8_8") (pintype "passive"))
      (node (ref "R41") (pin "1") (pinfunction "1_1") (pintype "passive"))
    )
    (net (code "112") (name "Net-(J5-Pad1)") (class "Default")
      (node (ref "J5") (pin "1") (pinfunction "1_1") (pintype "passive"))
      (node (ref "R42") (pin "1") (pinfunction "1_1") (pintype "passive"))
    )
    (net (code "113") (name "Net-(J5-Pad2)") (class "Default")
      (node (ref "J5") (pin "2") (pinfunction "2_2") (pintype "passive"))
      (node (ref "R43") (pin "1") (pinfunction "1_1") (pintype "passive"))
    )
    (net (code "114") (name "Net-(J5-Pad3)") (class "Default")
      (node (ref "J5") (pin "3") (pinfunction "3_3") (pintype "passive"))
      (node (ref "R44") (pin "1") (pinfunction "1_1") (pintype "passive"))
    )
    (net (code "115") (name "Net-(J5-Pad4)") (class "Default")
      (node (ref "J5") (pin "4") (pinfunction "4_4") (pintype "passive"))
      (node (ref "R45") (pin "1") (pinfunction "1_1") (pintype "passive"))
    )
    (net (code "116") (name "Net-(J5-Pad5)") (class "Default")
      (node (ref "J5") (pin "5") (pinfunction "5_5") (pintype "passive"))
      (node (ref "R46") (pin "1") (pinfunction "1_1") (pintype "passive"))
    )
    (net (code "117") (name "Net-(J5-Pad6)") (class "Default")
      (node (ref "J5") (pin "6") (pinfunction "6_6") (pintype "passive"))
      (node (ref "R47") (pin "1") (pinfunction "1_1") (pintype "passive"))
    )
    (net (code "118") (name "Net-(J5-Pad7)") (class "Default")
      (node (ref "J5") (pin "7") (pinfunction "7_7") (pintype "passive"))
      (node (ref "R48") (pin "1") (pinfunction "1_1") (pintype "passive"))
    )
    (net (code "119") (name "Net-(J5-Pad8)") (class "Default")
      (node (ref "J5") (pin "8") (pinfunction "8_8") (pintype "passive"))
      (node (ref "R49") (pin "1") (pinfunction "1_1") (pintype "passive"))
    )
    (net (code "120") (name "Net-(J6-Pad1)") (class "Default")
      (node (ref "J6") (pin "1") (pinfunction "1_1") (pintype "passive"))
      (node (ref "R50") (pin "1") (pinfunction "1_1") (pintype "passive"))
    )
    (net (code "121") (name "Net-(J6-Pad2)") (class "Default")
      (node (ref "J6") (pin "2") (pinfunction "2_2") (pintype "passive"))
      (node (ref "R51") (pin "1") (pinfunction "1_1") (pintype "passive"))
    )
    (net (code "122") (name "Net-(J6-Pad3)") (class "Default")
      (node (ref "J6") (pin "3") (pinfunction "3_3") (pintype "passive"))
      (node (ref "R52") (pin "1") (pinfunction "1_1") (pintype "passive"))
    )
    (net (code "123") (name "Net-(J6-Pad4)") (class "Default")
      (node (ref "J6") (pin "4") (pinfunction "4_4") (pintype "passive"))
      (node (ref "R53") (pin "1") (pinfunction "1_1") (pintype "passive"))
    )
    (net (code "124") (name "Net-(J6-Pad5)") (class "Default")
      (node (ref "J6") (pin "5") (pinfunction "5_5") (pintype "passive"))
      (node (ref "R54") (pin "1") (pinfunction "1_1") (pintype "passive"))
    )
    (net (code "125") (name "Net-(J6-Pad6)") (class "Default")
      (node (ref "J6") (pin "6") (pinfunction "6_6") (pintype "passive"))
      (node (ref "R55") (pin "1") (pinfunction "1_1") (pintype "passive"))
    )
    (net (code "126") (name "Net-(J6-Pad7)") (class "Default")
      (node (ref "J6") (pin "7") (pinfunction "7_7") (pintype "passive"))
      (node (ref "R56") (pin "1") (pinfunction "1_1") (pintype "passive"))
    )
    (net (code "127") (name "Net-(J6-Pad8)") (class "Default")
      (node (ref "J6") (pin "8") (pinfunction "8_8") (pintype "passive"))
      (node (ref "R57") (pin "1") (pinfunction "1_1") (pintype "passive"))
    )
    (net (code "128") (name "Net-(U1-IREF)") (class "Default")
      (node (ref "R1") (pin "1") (pinfunction "1_1") (pintype "passive"))
      (node (ref "U1") (pin "31") (pinfunction "IREF_31") (pintype "bidirectional"))
    )
    (net (code "129") (name "Net-(U2-IREF)") (class "Default")
      (node (ref "R2") (pin "1") (pinfunction "1_1") (pintype "passive"))
      (node (ref "U2") (pin "31") (pinfunction "IREF_31") (pintype "bidirectional"))
    )
    (net (code "130") (name "VCC") (class "Default")
      (node (ref "C1") (pin "1") (pinfunction "1_1") (pintype "passive"))
      (node (ref "C2") (pin "1") (pinfunction "1_1") (pintype "passive"))
      (node (ref "C3") (pin "1") (pinfunction "1_1") (pintype "passive"))
      (node (ref "C5") (pin "1") (pinfunction "1_1") (pintype "passive"))
      (node (ref "R3") (pin "1") (pinfunction "1_1") (pintype "passive"))
      (node (ref "R5") (pin "1") (pinfunction "1_1") (pintype "passive"))
      (node (ref "U1") (pin "32") (pinfunction "VCC_32") (pintype "bidirectional"))
      (node (ref "U2") (pin "32") (pinfunction "VCC_32") (pintype "bidirectional"))
      (node (ref "U7") (pin "5V") (pinfunction "5V_5V") (pintype "bidirectional"))
      (node (ref "U8") (pin "15") (pinfunction "VDD_15") (pintype "power_in"))
      (node (ref "U9") (pin "15") (pinfunction "VDD_15") (pintype "power_in"))
    )
    (net (code "131") (name "unconnected-(U2-SOUT-Pad29)") (class "Default")
      (node (ref "U2") (pin "29") (pinfunction "SOUT_29") (pintype "bidirectional"))
    )
    (net (code "132") (name "unconnected-(U7-*D3-PadD3)") (class "Default")
      (node (ref "U7") (pin "D3") (pinfunction "*D3_D3") (pintype "bidirectional"))
    )
    (net (code "133") (name "unconnected-(U7-Pad3.3V)") (class "Default")
      (node (ref "U7") (pin "3.3V") (pinfunction "3.3V_3.3V") (pintype "bidirectional"))
    )
    (net (code "134") (name "unconnected-(U7-PadA0)") (class "Default")
      (node (ref "U7") (pin "A0") (pinfunction "A0_A0") (pintype "bidirectional"))
    )
    (net (code "135") (name "unconnected-(U7-PadA1)") (class "Default")
      (node (ref "U7") (pin "A1") (pinfunction "A1_A1") (pintype "bidirectional"))
    )
    (net (code "136") (name "unconnected-(U7-PadA2)") (class "Default")
      (node (ref "U7") (pin "A2") (pinfunction "A2_A2") (pintype "bidirectional"))
    )
    (net (code "137") (name "unconnected-(U7-PadA3)") (class "Default")
      (node (ref "U7") (pin "A3") (pinfunction "A3_A3") (pintype "bidirectional"))
    )
    (net (code "138") (name "unconnected-(U7-PadAREF)") (class "Default")
      (node (ref "U7") (pin "AREF") (pinfunction "AREF_AREF") (pintype "bidirectional"))
    )
    (net (code "139") (name "unconnected-(U7-PadD2)") (class "Default")
      (node (ref "U7") (pin "D2") (pinfunction "D2_D2") (pintype "bidirectional"))
    )
    (net (code "140") (name "unconnected-(U7-PadD8)") (class "Default")
      (node (ref "U7") (pin "D8") (pinfunction "D8_D8") (pintype "bidirectional"))
    )
    (net (code "141") (name "unconnected-(U7-PadD13)") (class "Default")
      (node (ref "U7") (pin "D13") (pinfunction "D13_D13") (pintype "bidirectional"))
    )
    (net (code "142") (name "unconnected-(U7-PadIOREF)") (class "Default")
      (node (ref "U7") (pin "IOREF") (pinfunction "IOREF_IOREF") (pintype "bidirectional"))
    )
    (net (code "143") (name "unconnected-(U7-PadRES)") (class "Default")
      (node (ref "U7") (pin "RES") (pinfunction "RES_RES") (pintype "bidirectional"))
    )
    (net (code "144") (name "unconnected-(U7-PadRX)") (class "Default")
      (node (ref "U7") (pin "RX") (pinfunction "RX_RX") (pintype "bidirectional"))
    )
    (net (code "145") (name "unconnected-(U7-PadSCL)") (class "Default")
      (node (ref "U7") (pin "SCL") (pinfunction "SCL_SCL") (pintype "bidirectional"))
    )
    (net (code "146") (name "unconnected-(U7-PadSDA)") (class "Default")
      (node (ref "U7") (pin "SDA") (pinfunction "SDA_SDA") (pintype "bidirectional"))
    )
    (net (code "147") (name "unconnected-(U7-PadTX)") (class "Default")
      (node (ref "U7") (pin "TX") (pinfunction "TX_TX") (pintype "bidirectional"))
    )
    (net (code "148") (name "unconnected-(U7-PadVIN)") (class "Default")
      (node (ref "U7") (pin "VIN") (pinfunction "VIN_VIN") (pintype "bidirectional"))
    )
    (net (code "149") (name "unconnected-(U9-SDOUT-Pad16)") (class "Default")
      (node (ref "U9") (pin "16") (pinfunction "SDOUT_16") (pintype "output"))
    )
  )
)
